# Analog_adacus_sch.net
KiCad netlist of a schematic drawn in Altium Designer
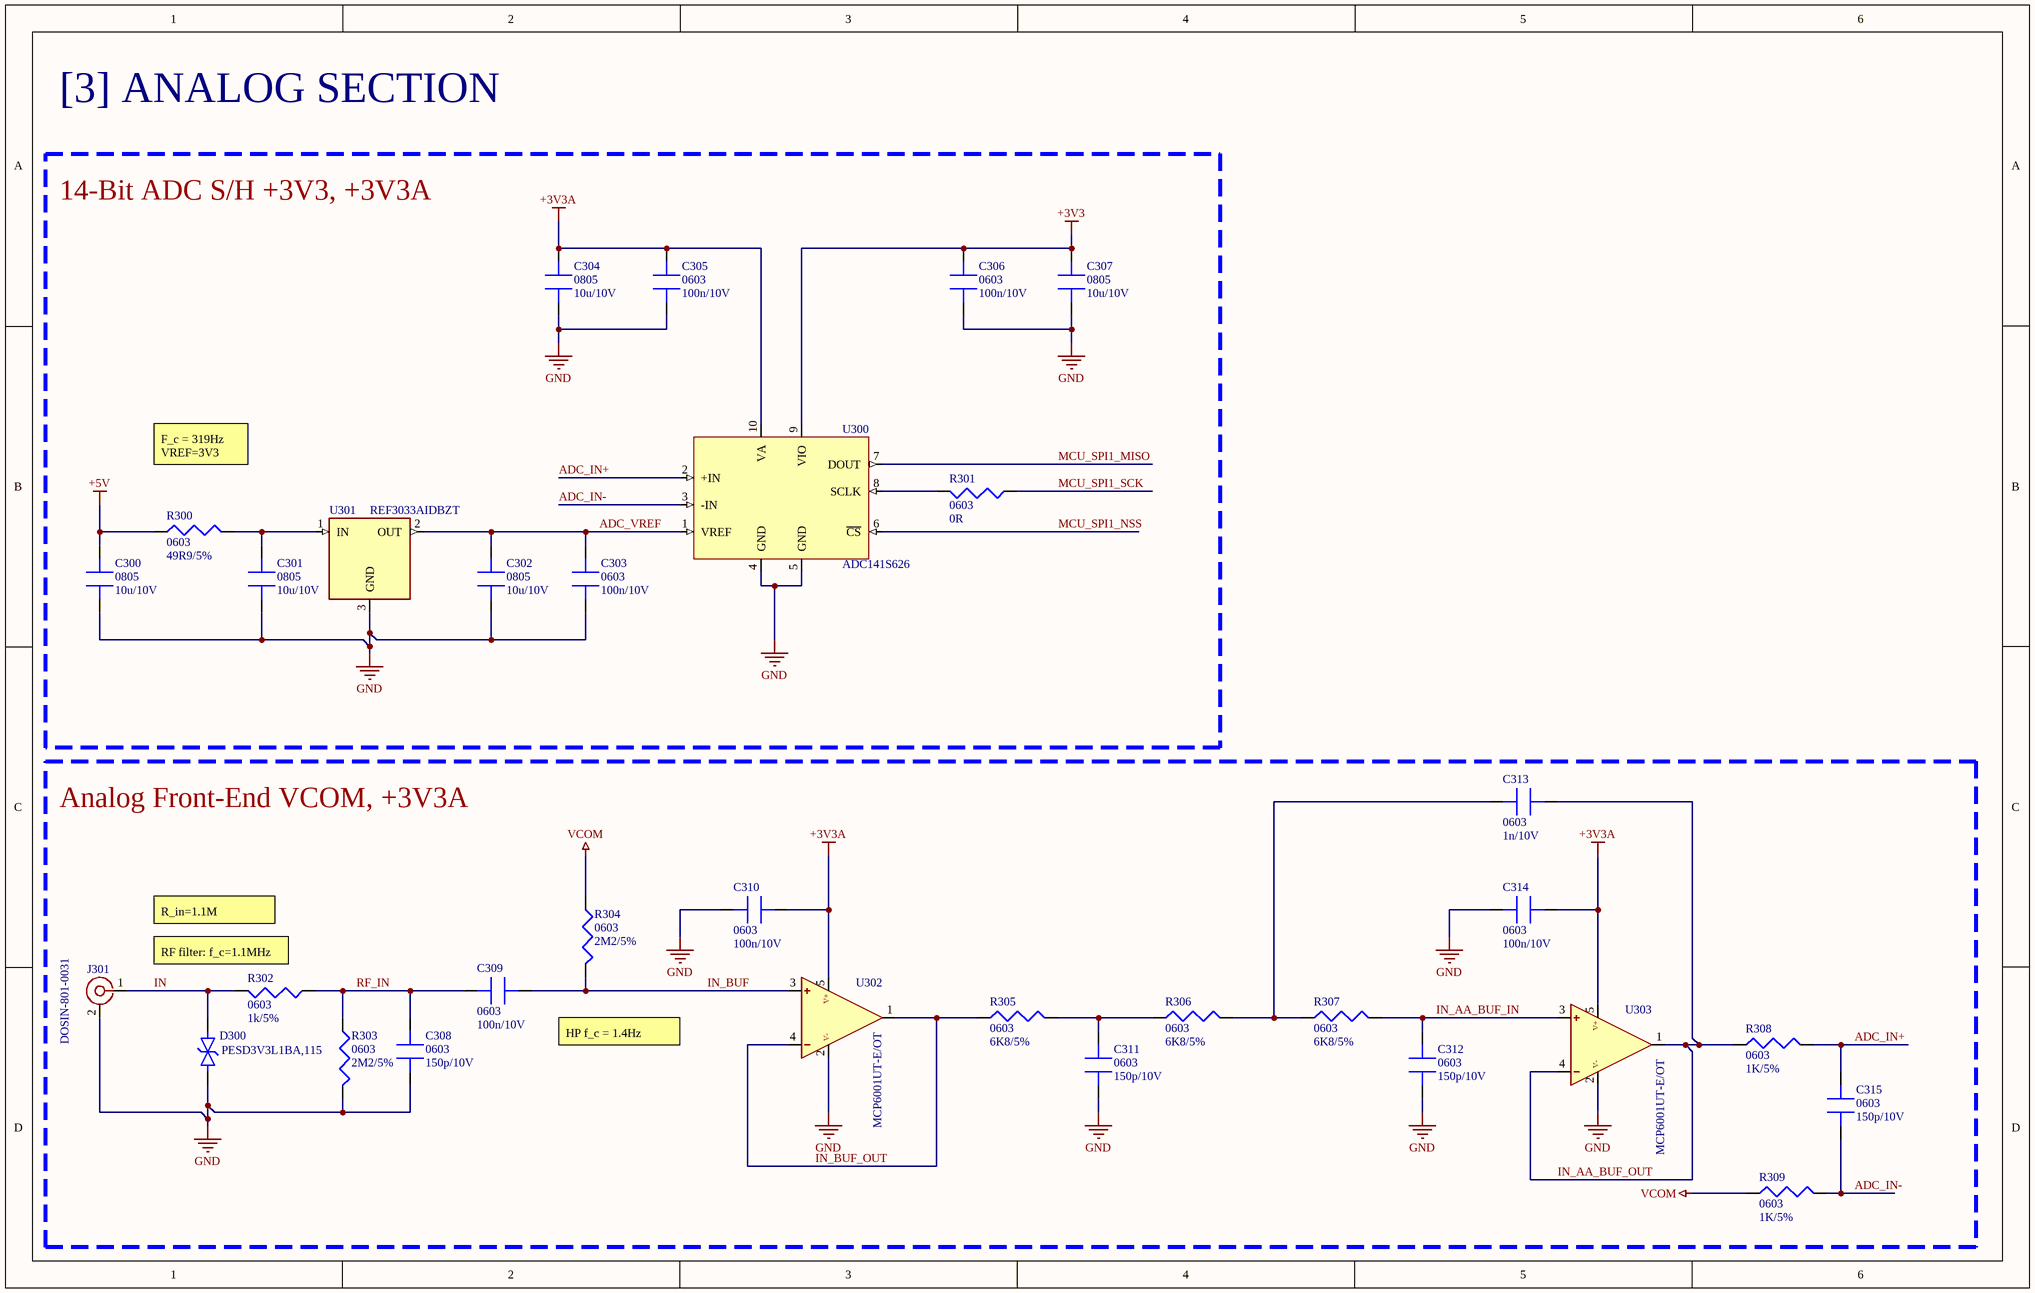
[diagram p0: Analog_adacus_sch.SchDoc]

(export (version "E")
  (design (tool "Eeschema 10.0.6"))
  (components
    (comp (ref "C300")
      (value "10u/10V")
      (footprint "[0805] CAPC2012X09M [A - LD]")
      (description "Standard Capacitor")
      (fields (field (name "PACKAGE") "0805") (field (name "Comment") "Capacitor"))
      (libsource (lib "adacus_schlib") (part "Capacitor"))
    )
    (comp (ref "C301")
      (value "10u/10V")
      (footprint "[0805] CAPC2012X09M [A - LD]")
      (description "Standard Capacitor")
      (fields (field (name "PACKAGE") "0805") (field (name "Comment") "Capacitor"))
      (libsource (lib "adacus_schlib") (part "Capacitor"))
    )
    (comp (ref "C302")
      (value "10u/10V")
      (footprint "[0805] CAPC2012X09M [A - LD]")
      (description "Standard Capacitor")
      (fields (field (name "PACKAGE") "0805") (field (name "Comment") "Capacitor"))
      (libsource (lib "adacus_schlib") (part "Capacitor"))
    )
    (comp (ref "C303")
      (value "100n/10V")
      (footprint "[0603] CAPC1608X10M [A-LD]")
      (description "Standard Capacitor")
      (fields (field (name "PACKAGE") "0603") (field (name "Comment") "Capacitor"))
      (libsource (lib "adacus_schlib") (part "Capacitor"))
    )
    (comp (ref "C304")
      (value "10u/10V")
      (footprint "[0805] CAPC2012X09M [A - LD]")
      (description "Standard Capacitor")
      (fields (field (name "PACKAGE") "0805") (field (name "Comment") "Capacitor"))
      (libsource (lib "adacus_schlib") (part "Capacitor"))
    )
    (comp (ref "C305")
      (value "100n/10V")
      (footprint "[0603] CAPC1608X10M [A-LD]")
      (description "Standard Capacitor")
      (fields (field (name "PACKAGE") "0603") (field (name "Comment") "Capacitor"))
      (libsource (lib "adacus_schlib") (part "Capacitor"))
    )
    (comp (ref "C306")
      (value "100n/10V")
      (footprint "[0603] CAPC1608X10M [A-LD]")
      (description "Standard Capacitor")
      (fields (field (name "PACKAGE") "0603") (field (name "Comment") "Capacitor"))
      (libsource (lib "adacus_schlib") (part "Capacitor"))
    )
    (comp (ref "C307")
      (value "10u/10V")
      (footprint "[0805] CAPC2012X09M [A - LD]")
      (description "Standard Capacitor")
      (fields (field (name "PACKAGE") "0805") (field (name "Comment") "Capacitor"))
      (libsource (lib "adacus_schlib") (part "Capacitor"))
    )
    (comp (ref "C308")
      (value "150p/10V")
      (footprint "[0603] CAPC1608X10M [A-LD]")
      (description "Standard Capacitor")
      (fields (field (name "PACKAGE") "0603") (field (name "Comment") "Capacitor"))
      (libsource (lib "adacus_schlib") (part "Capacitor"))
    )
    (comp (ref "C309")
      (value "100n/10V")
      (footprint "[0603] CAPC1608X10M [A-LD]")
      (description "Standard Capacitor")
      (fields (field (name "PACKAGE") "0603") (field (name "Comment") "Capacitor"))
      (libsource (lib "adacus_schlib") (part "Capacitor"))
    )
    (comp (ref "C310")
      (value "100n/10V")
      (footprint "[0603] CAPC1608X10M [A-LD]")
      (description "Standard Capacitor")
      (fields (field (name "PACKAGE") "0603") (field (name "Comment") "Capacitor"))
      (libsource (lib "adacus_schlib") (part "Capacitor"))
    )
    (comp (ref "C311")
      (value "150p/10V")
      (footprint "[0603] CAPC1608X10M [A-LD]")
      (description "Standard Capacitor")
      (fields (field (name "PACKAGE") "0603") (field (name "Comment") "Capacitor"))
      (libsource (lib "adacus_schlib") (part "Capacitor"))
    )
    (comp (ref "C312")
      (value "150p/10V")
      (footprint "[0603] CAPC1608X10M [A-LD]")
      (description "Standard Capacitor")
      (fields (field (name "PACKAGE") "0603") (field (name "Comment") "Capacitor"))
      (libsource (lib "adacus_schlib") (part "Capacitor"))
    )
    (comp (ref "C313")
      (value "1n/10V")
      (footprint "[0603] CAPC1608X10M [A-LD]")
      (description "Standard Capacitor")
      (fields (field (name "PACKAGE") "0603") (field (name "Comment") "Capacitor"))
      (libsource (lib "adacus_schlib") (part "Capacitor"))
    )
    (comp (ref "C314")
      (value "100n/10V")
      (footprint "[0603] CAPC1608X10M [A-LD]")
      (description "Standard Capacitor")
      (fields (field (name "PACKAGE") "0603") (field (name "Comment") "Capacitor"))
      (libsource (lib "adacus_schlib") (part "Capacitor"))
    )
    (comp (ref "C315")
      (value "150p/10V")
      (footprint "[0603] CAPC1608X10M [A-LD]")
      (description "Standard Capacitor")
      (fields (field (name "PACKAGE") "0603") (field (name "Comment") "Capacitor"))
      (libsource (lib "adacus_schlib") (part "Capacitor"))
    )
    (comp (ref "D300")
      (value "PESD3V3L1BA,115")
      (footprint "SODFL250X110-2M")
      (description "ESD Suppressors / TVS Diodes PESD3V3L1BA/SOD323/SOD2")
      (libsource (lib "adacus_schlib") (part "PESD3V3L1BA,115"))
    )
    (comp (ref "J301")
      (value "DOSIN-801-0031")
      (footprint "DOSIN8010031")
      (description "BNC Board Edge Bend 9.6mm Plugin RF Connectors / Coaxial Connectors")
      (libsource (lib "adacus_schlib") (part "BNC Connector"))
    )
    (comp (ref "R300")
      (value "49R9/5%")
      (footprint "[0603] RESC1608X06M [A-LD]")
      (description "Standard Resistor")
      (fields (field (name "PACKAGE") "0603") (field (name "Comment") "Resistor"))
      (libsource (lib "adacus_schlib") (part "Resistor"))
    )
    (comp (ref "R301")
      (value "0R")
      (footprint "[0603] RESC1608X06M [A-LD]")
      (description "Standard Resistor")
      (fields (field (name "PACKAGE") "0603") (field (name "Comment") "Resistor"))
      (libsource (lib "adacus_schlib") (part "Resistor"))
    )
    (comp (ref "R302")
      (value "1k/5%")
      (footprint "[0603] RESC1608X06M [A-LD]")
      (description "Standard Resistor")
      (fields (field (name "PACKAGE") "0603") (field (name "Comment") "Resistor"))
      (libsource (lib "adacus_schlib") (part "Resistor"))
    )
    (comp (ref "R303")
      (value "2M2/5%")
      (footprint "[0603] RESC1608X06M [A-LD]")
      (description "Standard Resistor")
      (fields (field (name "PACKAGE") "0603") (field (name "Comment") "Resistor"))
      (libsource (lib "adacus_schlib") (part "Resistor"))
    )
    (comp (ref "R304")
      (value "2M2/5%")
      (footprint "[0603] RESC1608X06M [A-LD]")
      (description "Standard Resistor")
      (fields (field (name "PACKAGE") "0603") (field (name "Comment") "Resistor"))
      (libsource (lib "adacus_schlib") (part "Resistor"))
    )
    (comp (ref "R305")
      (value "6K8/5%")
      (footprint "[0603] RESC1608X06M [A-LD]")
      (description "Standard Resistor")
      (fields (field (name "PACKAGE") "0603") (field (name "Comment") "Resistor"))
      (libsource (lib "adacus_schlib") (part "Resistor"))
    )
    (comp (ref "R306")
      (value "6K8/5%")
      (footprint "[0603] RESC1608X06M [A-LD]")
      (description "Standard Resistor")
      (fields (field (name "PACKAGE") "0603") (field (name "Comment") "Resistor"))
      (libsource (lib "adacus_schlib") (part "Resistor"))
    )
    (comp (ref "R307")
      (value "6K8/5%")
      (footprint "[0603] RESC1608X06M [A-LD]")
      (description "Standard Resistor")
      (fields (field (name "PACKAGE") "0603") (field (name "Comment") "Resistor"))
      (libsource (lib "adacus_schlib") (part "Resistor"))
    )
    (comp (ref "R308")
      (value "1K/5%")
      (footprint "[0603] RESC1608X06M [A-LD]")
      (description "Standard Resistor")
      (fields (field (name "PACKAGE") "0603") (field (name "Comment") "Resistor"))
      (libsource (lib "adacus_schlib") (part "Resistor"))
    )
    (comp (ref "R309")
      (value "1K/5%")
      (footprint "[0603] RESC1608X06M [A-LD]")
      (description "Standard Resistor")
      (fields (field (name "PACKAGE") "0603") (field (name "Comment") "Resistor"))
      (libsource (lib "adacus_schlib") (part "Resistor"))
    )
    (comp (ref "U300")
      (value "ADC141S626")
      (footprint "TSSOP50P490X110-10M")
      (libsource (lib "adacus_schlib") (part "ADC141S626"))
    )
    (comp (ref "U301")
      (value "REF3033AIDBZT")
      (footprint "SOT95P237X112-3M")
      (description "Voltage References 3.3V 50ppm/DegC 50uA SOT23-3 Series")
      (libsource (lib "adacus_schlib") (part "REF3033AIDBZT"))
    )
    (comp (ref "U302")
      (value "MCP6001UT-E/OT")
      (footprint "SOT95P270X145-5M")
      (description "Operational Amplifiers - Op Amps Single 1.8V 1MHz")
      (libsource (lib "adacus_schlib") (part "MCP6001UT-E/OT"))
    )
    (comp (ref "U303")
      (value "MCP6001UT-E/OT")
      (footprint "SOT95P270X145-5M")
      (description "Operational Amplifiers - Op Amps Single 1.8V 1MHz")
      (libsource (lib "adacus_schlib") (part "MCP6001UT-E/OT"))
    )
  )
  (nets
    (net (code "1") (name "+3V3") (class "Default")
      (node (ref "C306") (pin "2") (pinfunction "2_2") (pintype "passive"))
      (node (ref "C307") (pin "2") (pinfunction "2_2") (pintype "passive"))
      (node (ref "U300") (pin "9") (pinfunction "VIO_9") (pintype "power_in"))
    )
    (net (code "2") (name "+3V3A") (class "Default")
      (node (ref "C304") (pin "2") (pinfunction "2_2") (pintype "passive"))
      (node (ref "C305") (pin "2") (pinfunction "2_2") (pintype "passive"))
      (node (ref "C310") (pin "1") (pinfunction "1_1") (pintype "passive"))
      (node (ref "C314") (pin "1") (pinfunction "1_1") (pintype "passive"))
      (node (ref "U300") (pin "10") (pinfunction "VA_10") (pintype "power_in"))
      (node (ref "U302") (pin "5") (pinfunction "VDD_5") (pintype "passive"))
      (node (ref "U303") (pin "5") (pinfunction "VDD_5") (pintype "passive"))
    )
    (net (code "3") (name "+5V") (class "Default")
      (node (ref "C300") (pin "2") (pinfunction "2_2") (pintype "passive"))
      (node (ref "R300") (pin "2") (pinfunction "2_2") (pintype "passive"))
    )
    (net (code "4") (name "/ADC_IN+") (class "Default")
      (node (ref "C315") (pin "2") (pinfunction "2_2") (pintype "passive"))
      (node (ref "R308") (pin "1") (pinfunction "1_1") (pintype "passive"))
      (node (ref "U300") (pin "2") (pinfunction "+IN_2") (pintype "input"))
    )
    (net (code "5") (name "/ADC_IN-") (class "Default")
      (node (ref "C315") (pin "1") (pinfunction "1_1") (pintype "passive"))
      (node (ref "R309") (pin "1") (pinfunction "1_1") (pintype "passive"))
      (node (ref "U300") (pin "3") (pinfunction "-IN_3") (pintype "input"))
    )
    (net (code "6") (name "/ADC_VREF") (class "Default")
      (node (ref "C302") (pin "2") (pinfunction "2_2") (pintype "passive"))
      (node (ref "C303") (pin "2") (pinfunction "2_2") (pintype "passive"))
      (node (ref "U300") (pin "1") (pinfunction "VREF_1") (pintype "input"))
      (node (ref "U301") (pin "2") (pinfunction "OUT_2") (pintype "output"))
    )
    (net (code "7") (name "/IN") (class "Default")
      (node (ref "D300") (pin "2") (pinfunction "2_2") (pintype "passive"))
      (node (ref "J301") (pin "1") (pinfunction "1_1") (pintype "passive"))
      (node (ref "R302") (pin "1") (pinfunction "1_1") (pintype "passive"))
    )
    (net (code "8") (name "/IN_AA_BUF_IN") (class "Default")
      (node (ref "C312") (pin "2") (pinfunction "2_2") (pintype "passive"))
      (node (ref "R307") (pin "1") (pinfunction "1_1") (pintype "passive"))
      (node (ref "U303") (pin "3") (pinfunction "+_3") (pintype "passive"))
    )
    (net (code "9") (name "/IN_AA_BUF_OUT") (class "Default")
      (node (ref "C313") (pin "1") (pinfunction "1_1") (pintype "passive"))
      (node (ref "R308") (pin "2") (pinfunction "2_2") (pintype "passive"))
      (node (ref "U303") (pin "1") (pinfunction "OUT_1") (pintype "passive"))
      (node (ref "U303") (pin "4") (pinfunction "-_4") (pintype "passive"))
    )
    (net (code "10") (name "/IN_BUF") (class "Default")
      (node (ref "C309") (pin "1") (pinfunction "1_1") (pintype "passive"))
      (node (ref "R304") (pin "1") (pinfunction "1_1") (pintype "passive"))
      (node (ref "U302") (pin "3") (pinfunction "+_3") (pintype "passive"))
    )
    (net (code "11") (name "/IN_BUF_OUT") (class "Default")
      (node (ref "R305") (pin "2") (pinfunction "2_2") (pintype "passive"))
      (node (ref "U302") (pin "1") (pinfunction "OUT_1") (pintype "passive"))
      (node (ref "U302") (pin "4") (pinfunction "-_4") (pintype "passive"))
    )
    (net (code "12") (name "/MCU_SPI1_MISO") (class "Default")
      (node (ref "U300") (pin "7") (pinfunction "DOUT_7") (pintype "output"))
    )
    (net (code "13") (name "/MCU_SPI1_NSS") (class "Default")
      (node (ref "U300") (pin "6") (pinfunction "~{CS}_6") (pintype "input"))
    )
    (net (code "14") (name "/MCU_SPI1_SCK") (class "Default")
      (node (ref "R301") (pin "2") (pinfunction "2_2") (pintype "passive"))
    )
    (net (code "15") (name "/RF_IN") (class "Default")
      (node (ref "C308") (pin "2") (pinfunction "2_2") (pintype "passive"))
      (node (ref "C309") (pin "2") (pinfunction "2_2") (pintype "passive"))
      (node (ref "R302") (pin "2") (pinfunction "2_2") (pintype "passive"))
      (node (ref "R303") (pin "2") (pinfunction "2_2") (pintype "passive"))
    )
    (net (code "16") (name "GND") (class "Default")
      (node (ref "C300") (pin "1") (pinfunction "1_1") (pintype "passive"))
      (node (ref "C301") (pin "1") (pinfunction "1_1") (pintype "passive"))
      (node (ref "C302") (pin "1") (pinfunction "1_1") (pintype "passive"))
      (node (ref "C303") (pin "1") (pinfunction "1_1") (pintype "passive"))
      (node (ref "C304") (pin "1") (pinfunction "1_1") (pintype "passive"))
      (node (ref "C305") (pin "1") (pinfunction "1_1") (pintype "passive"))
      (node (ref "C306") (pin "1") (pinfunction "1_1") (pintype "passive"))
      (node (ref "C307") (pin "1") (pinfunction "1_1") (pintype "passive"))
      (node (ref "C308") (pin "1") (pinfunction "1_1") (pintype "passive"))
      (node (ref "C310") (pin "2") (pinfunction "2_2") (pintype "passive"))
      (node (ref "C311") (pin "1") (pinfunction "1_1") (pintype "passive"))
      (node (ref "C312") (pin "1") (pinfunction "1_1") (pintype "passive"))
      (node (ref "C314") (pin "2") (pinfunction "2_2") (pintype "passive"))
      (node (ref "D300") (pin "1") (pinfunction "1_1") (pintype "passive"))
      (node (ref "J301") (pin "2") (pinfunction "2_2") (pintype "passive"))
      (node (ref "R303") (pin "1") (pinfunction "1_1") (pintype "passive"))
      (node (ref "U300") (pin "4") (pinfunction "GND_4") (pintype "power_in"))
      (node (ref "U300") (pin "5") (pinfunction "GND_5") (pintype "power_in"))
      (node (ref "U301") (pin "3") (pinfunction "GND_3") (pintype "power_in"))
      (node (ref "U302") (pin "2") (pinfunction "VSS_2") (pintype "passive"))
      (node (ref "U303") (pin "2") (pinfunction "VSS_2") (pintype "passive"))
    )
    (net (code "17") (name "Net-(C311-Pad2)") (class "Default")
      (node (ref "C311") (pin "2") (pinfunction "2_2") (pintype "passive"))
      (node (ref "R305") (pin "1") (pinfunction "1_1") (pintype "passive"))
      (node (ref "R306") (pin "2") (pinfunction "2_2") (pintype "passive"))
    )
    (net (code "18") (name "Net-(C313-Pad2)") (class "Default")
      (node (ref "C313") (pin "2") (pinfunction "2_2") (pintype "passive"))
      (node (ref "R306") (pin "1") (pinfunction "1_1") (pintype "passive"))
      (node (ref "R307") (pin "2") (pinfunction "2_2") (pintype "passive"))
    )
    (net (code "19") (name "Net-(U300-SCLK)") (class "Default")
      (node (ref "R301") (pin "1") (pinfunction "1_1") (pintype "passive"))
      (node (ref "U300") (pin "8") (pinfunction "SCLK_8") (pintype "input"))
    )
    (net (code "20") (name "Net-(U301-IN)") (class "Default")
      (node (ref "C301") (pin "2") (pinfunction "2_2") (pintype "passive"))
      (node (ref "R300") (pin "1") (pinfunction "1_1") (pintype "passive"))
      (node (ref "U301") (pin "1") (pinfunction "IN_1") (pintype "input"))
    )
    (net (code "21") (name "VCOM") (class "Default")
      (node (ref "R304") (pin "2") (pinfunction "2_2") (pintype "passive"))
      (node (ref "R309") (pin "2") (pinfunction "2_2") (pintype "passive"))
    )
  )
)
